# OpenROV_Light_Board_2_8A.net
KiCad netlist of a schematic drawn in EAGLE
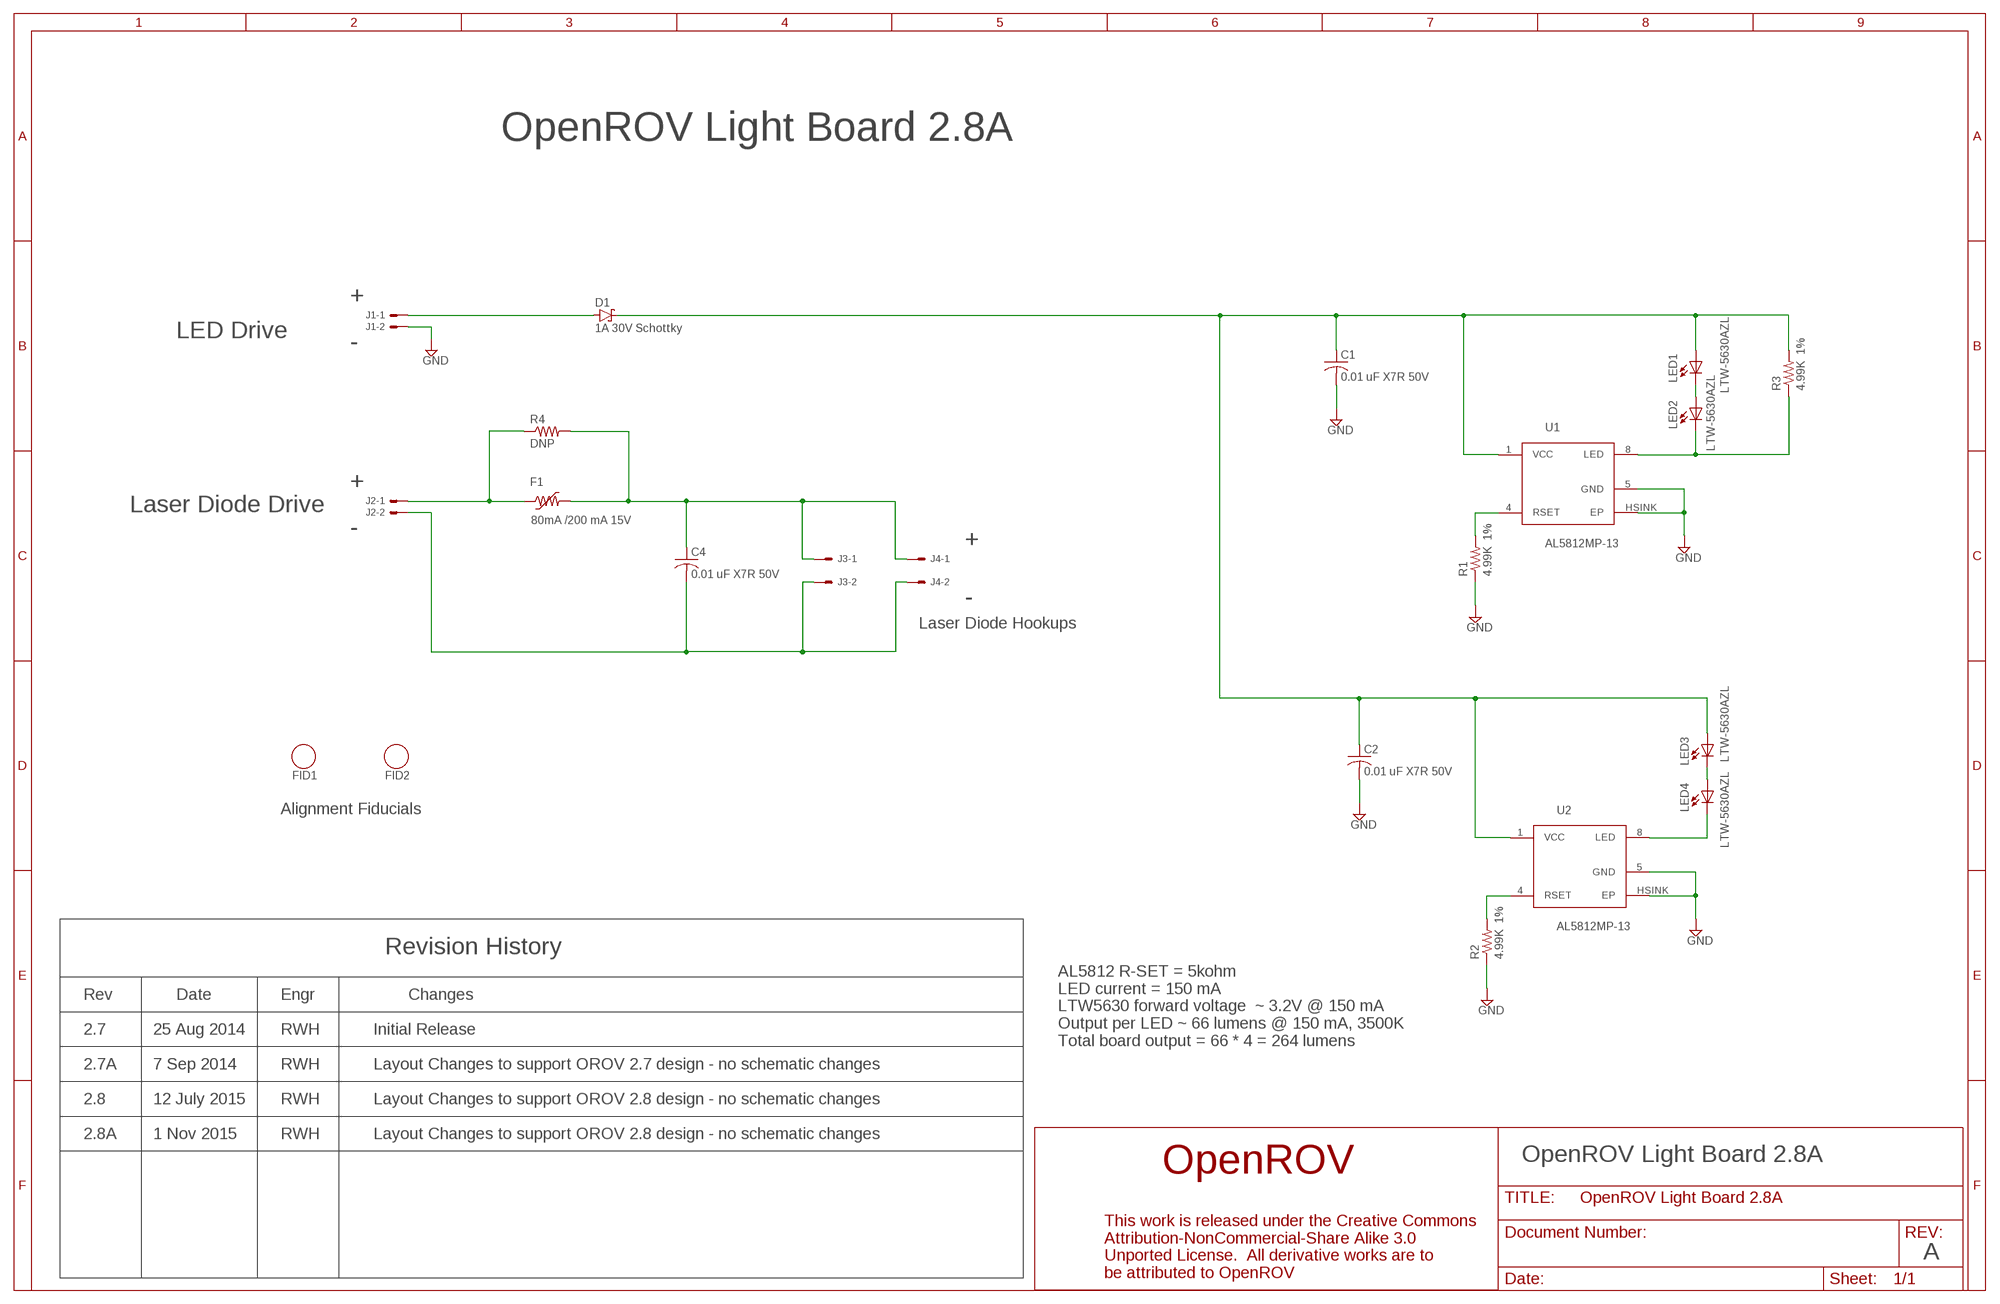
[diagram p0: schematic, sheet 1]

(export (version "E")
  (design (tool "Eeschema 10.0.6"))
  (components
    (comp (ref "C1")
      (value "0.01 uF X7R 50V")
      (footprint "eagle-import:R0603")
      (libsource (lib "eagle-import") (part "CAP0603"))
    )
    (comp (ref "C2")
      (value "0.01 uF X7R 50V")
      (footprint "eagle-import:R0603")
      (libsource (lib "eagle-import") (part "CAP0603"))
    )
    (comp (ref "C4")
      (value "0.01 uF X7R 50V")
      (footprint "eagle-import:R0603")
      (libsource (lib "eagle-import") (part "CAP0603"))
    )
    (comp (ref "D1")
      (value "1A 30V Schottky")
      (footprint "eagle-import:DO214AC")
      (libsource (lib "eagle-import") (part "SCHOTTKYDO214AC"))
    )
    (comp (ref "F1")
      (value "80mA /200 mA 15V")
      (footprint "eagle-import:R0603")
      (libsource (lib "eagle-import") (part "POLYFUSE-0603"))
    )
    (comp (ref "FID1")
      (value "FIDUCIAL_1")
      (footprint "eagle-import:FIDUCIAL_1")
      (libsource (lib "eagle-import") (part "FIDUCIAL_1"))
    )
    (comp (ref "FID2")
      (value "FIDUCIAL_1")
      (footprint "eagle-import:FIDUCIAL_1")
      (libsource (lib "eagle-import") (part "FIDUCIAL_1"))
    )
    (comp (ref "J1")
      (value "SOLDER_PADS_3MM")
      (footprint "eagle-import:SOLDER_PADS_3MM")
      (libsource (lib "eagle-import") (part "SOLDER_PADS_3MM"))
    )
    (comp (ref "J2")
      (value "SOLDER_PADS_3MM")
      (footprint "eagle-import:SOLDER_PADS_3MM")
      (libsource (lib "eagle-import") (part "SOLDER_PADS_3MM"))
    )
    (comp (ref "J3")
      (value "SOLDER_PADS_3MM-SMALL_HOLE")
      (footprint "eagle-import:SOLDER_PADS_3MM_SMALL_HOLE")
      (libsource (lib "eagle-import") (part "SOLDER_PADS_3MM-SMALL_HOLE"))
    )
    (comp (ref "J4")
      (value "SOLDER_PADS_3MM-SMALL_HOLE")
      (footprint "eagle-import:SOLDER_PADS_3MM_SMALL_HOLE")
      (libsource (lib "eagle-import") (part "SOLDER_PADS_3MM-SMALL_HOLE"))
    )
    (comp (ref "LED1")
      (value "LTW-5630AZL")
      (footprint "eagle-import:LITEON-5630")
      (libsource (lib "eagle-import") (part "LTW-5630AZL"))
    )
    (comp (ref "LED2")
      (value "LTW-5630AZL")
      (footprint "eagle-import:LITEON-5630")
      (libsource (lib "eagle-import") (part "LTW-5630AZL"))
    )
    (comp (ref "LED3")
      (value "LTW-5630AZL")
      (footprint "eagle-import:LITEON-5630")
      (libsource (lib "eagle-import") (part "LTW-5630AZL"))
    )
    (comp (ref "LED4")
      (value "LTW-5630AZL")
      (footprint "eagle-import:LITEON-5630")
      (libsource (lib "eagle-import") (part "LTW-5630AZL"))
    )
    (comp (ref "R1")
      (value "4.99K 1%")
      (footprint "eagle-import:R0603")
      (libsource (lib "eagle-import") (part "RESISTOR-0603"))
    )
    (comp (ref "R2")
      (value "4.99K 1%")
      (footprint "eagle-import:R0603")
      (libsource (lib "eagle-import") (part "RESISTOR-0603"))
    )
    (comp (ref "R3")
      (value "4.99K 1%")
      (footprint "eagle-import:R0603")
      (libsource (lib "eagle-import") (part "RESISTOR-0603"))
    )
    (comp (ref "R4")
      (value "DNP")
      (footprint "eagle-import:R1206")
      (libsource (lib "eagle-import") (part "RESISTOR-1206"))
    )
    (comp (ref "U1")
      (value "AL5812MP-13")
      (footprint "eagle-import:MSOP-8EP")
      (libsource (lib "eagle-import") (part "AL5812MP-13"))
    )
    (comp (ref "U2")
      (value "AL5812MP-13")
      (footprint "eagle-import:MSOP-8EP")
      (libsource (lib "eagle-import") (part "AL5812MP-13"))
    )
  )
  (nets
    (net (code "1") (name "GND") (class "Default")
      (node (ref "C1") (pin "2") (pinfunction "2_2") (pintype "passive"))
      (node (ref "C2") (pin "2") (pinfunction "2_2") (pintype "passive"))
      (node (ref "J1") (pin "2") (pinfunction "S_2") (pintype "passive"))
      (node (ref "R1") (pin "1") (pinfunction "1_1") (pintype "passive"))
      (node (ref "R2") (pin "1") (pinfunction "1_1") (pintype "passive"))
      (node (ref "U1") (pin "5") (pinfunction "GND_5") (pintype "bidirectional"))
      (node (ref "U1") (pin "HSINK") (pinfunction "EP_HSINK") (pintype "bidirectional"))
      (node (ref "U2") (pin "5") (pinfunction "GND_5") (pintype "bidirectional"))
      (node (ref "U2") (pin "HSINK") (pinfunction "EP_HSINK") (pintype "bidirectional"))
    )
    (net (code "2") (name "Net-(J1A-S)") (class "Default")
      (node (ref "D1") (pin "A") (pinfunction "A_A") (pintype "passive"))
      (node (ref "J1") (pin "1") (pinfunction "S_1") (pintype "passive"))
    )
    (net (code "3") (name "Net-(J2A-S)") (class "Default")
      (node (ref "F1") (pin "1") (pinfunction "1_1") (pintype "passive"))
      (node (ref "J2") (pin "1") (pinfunction "S_1") (pintype "passive"))
      (node (ref "R4") (pin "1") (pinfunction "1_1") (pintype "passive"))
    )
    (net (code "4") (name "Net-(J2B-S)") (class "Default")
      (node (ref "C4") (pin "2") (pinfunction "2_2") (pintype "passive"))
      (node (ref "J2") (pin "2") (pinfunction "S_2") (pintype "passive"))
      (node (ref "J3") (pin "2") (pinfunction "S_2") (pintype "passive"))
      (node (ref "J4") (pin "2") (pinfunction "S_2") (pintype "passive"))
    )
    (net (code "5") (name "Net-(J3A-S)") (class "Default")
      (node (ref "C4") (pin "1") (pinfunction "1_1") (pintype "passive"))
      (node (ref "F1") (pin "2") (pinfunction "2_2") (pintype "passive"))
      (node (ref "J3") (pin "1") (pinfunction "S_1") (pintype "passive"))
      (node (ref "J4") (pin "1") (pinfunction "S_1") (pintype "passive"))
      (node (ref "R4") (pin "2") (pinfunction "2_2") (pintype "passive"))
    )
    (net (code "6") (name "Net-(LED1-C-PadC1)") (class "Default")
      (node (ref "LED1") (pin "C1") (pinfunction "C_C1") (pintype "passive"))
      (node (ref "LED1") (pin "C2") (pinfunction "C_C2") (pintype "passive"))
      (node (ref "LED2") (pin "A1") (pinfunction "A_A1") (pintype "passive"))
      (node (ref "LED2") (pin "A2") (pinfunction "A_A2") (pintype "passive"))
      (node (ref "LED2") (pin "A3") (pinfunction "A_A3") (pintype "passive"))
    )
    (net (code "7") (name "Net-(LED3-C-PadC1)") (class "Default")
      (node (ref "LED3") (pin "C1") (pinfunction "C_C1") (pintype "passive"))
      (node (ref "LED3") (pin "C2") (pinfunction "C_C2") (pintype "passive"))
      (node (ref "LED4") (pin "A1") (pinfunction "A_A1") (pintype "passive"))
      (node (ref "LED4") (pin "A2") (pinfunction "A_A2") (pintype "passive"))
      (node (ref "LED4") (pin "A3") (pinfunction "A_A3") (pintype "passive"))
    )
    (net (code "8") (name "Net-(U1-LED)") (class "Default")
      (node (ref "LED2") (pin "C1") (pinfunction "C_C1") (pintype "passive"))
      (node (ref "LED2") (pin "C2") (pinfunction "C_C2") (pintype "passive"))
      (node (ref "R3") (pin "1") (pinfunction "1_1") (pintype "passive"))
      (node (ref "U1") (pin "8") (pinfunction "LED_8") (pintype "bidirectional"))
    )
    (net (code "9") (name "Net-(U1-RSET)") (class "Default")
      (node (ref "R1") (pin "2") (pinfunction "2_2") (pintype "passive"))
      (node (ref "U1") (pin "4") (pinfunction "RSET_4") (pintype "bidirectional"))
    )
    (net (code "10") (name "Net-(U1-VCC)") (class "Default")
      (node (ref "C1") (pin "1") (pinfunction "1_1") (pintype "passive"))
      (node (ref "C2") (pin "1") (pinfunction "1_1") (pintype "passive"))
      (node (ref "D1") (pin "C") (pinfunction "C_C") (pintype "passive"))
      (node (ref "LED1") (pin "A1") (pinfunction "A_A1") (pintype "passive"))
      (node (ref "LED1") (pin "A2") (pinfunction "A_A2") (pintype "passive"))
      (node (ref "LED1") (pin "A3") (pinfunction "A_A3") (pintype "passive"))
      (node (ref "LED3") (pin "A1") (pinfunction "A_A1") (pintype "passive"))
      (node (ref "LED3") (pin "A2") (pinfunction "A_A2") (pintype "passive"))
      (node (ref "LED3") (pin "A3") (pinfunction "A_A3") (pintype "passive"))
      (node (ref "R3") (pin "2") (pinfunction "2_2") (pintype "passive"))
      (node (ref "U1") (pin "1") (pinfunction "VCC_1") (pintype "bidirectional"))
      (node (ref "U2") (pin "1") (pinfunction "VCC_1") (pintype "bidirectional"))
    )
    (net (code "11") (name "Net-(U2-LED)") (class "Default")
      (node (ref "LED4") (pin "C1") (pinfunction "C_C1") (pintype "passive"))
      (node (ref "LED4") (pin "C2") (pinfunction "C_C2") (pintype "passive"))
      (node (ref "U2") (pin "8") (pinfunction "LED_8") (pintype "bidirectional"))
    )
    (net (code "12") (name "Net-(U2-RSET)") (class "Default")
      (node (ref "R2") (pin "2") (pinfunction "2_2") (pintype "passive"))
      (node (ref "U2") (pin "4") (pinfunction "RSET_4") (pintype "bidirectional"))
    )
  )
)
